# single_led.net
KiCad netlist of a schematic drawn in EAGLE
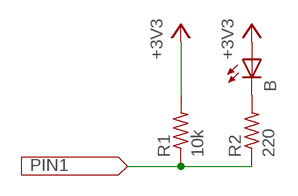
[diagram p0: schematic, sheet 1]

(export (version "E")
  (design (tool "Eeschema 10.0.6"))
  (components
    (comp (ref "B")
      (value "LED5MM")
      (footprint "eagle-import:LED5MM")
      (libsource (lib "eagle-import") (part "LED5MM"))
    )
    (comp (ref "R1")
      (value "10k")
      (footprint "eagle-import:0411_12")
      (libsource (lib "eagle-import") (part "R-US_0411/12"))
    )
    (comp (ref "R2")
      (value "220")
      (footprint "eagle-import:0411_12")
      (libsource (lib "eagle-import") (part "R-US_0411/12"))
    )
  )
  (nets
    (net (code "1") (name "+3V3") (class "Default")
      (node (ref "B") (pin "A") (pinfunction "A_A") (pintype "passive"))
      (node (ref "R1") (pin "2") (pinfunction "2_2") (pintype "passive"))
    )
    (net (code "2") (name "Net-(B-C)") (class "Default")
      (node (ref "B") (pin "K") (pinfunction "C_K") (pintype "passive"))
      (node (ref "R2") (pin "2") (pinfunction "2_2") (pintype "passive"))
    )
    (net (code "3") (name "Net-(R1-Pad1)") (class "Default")
      (node (ref "R1") (pin "1") (pinfunction "1_1") (pintype "passive"))
      (node (ref "R2") (pin "1") (pinfunction "1_1") (pintype "passive"))
    )
  )
)
